# robot.net
KiCad netlist of a schematic drawn in EAGLE
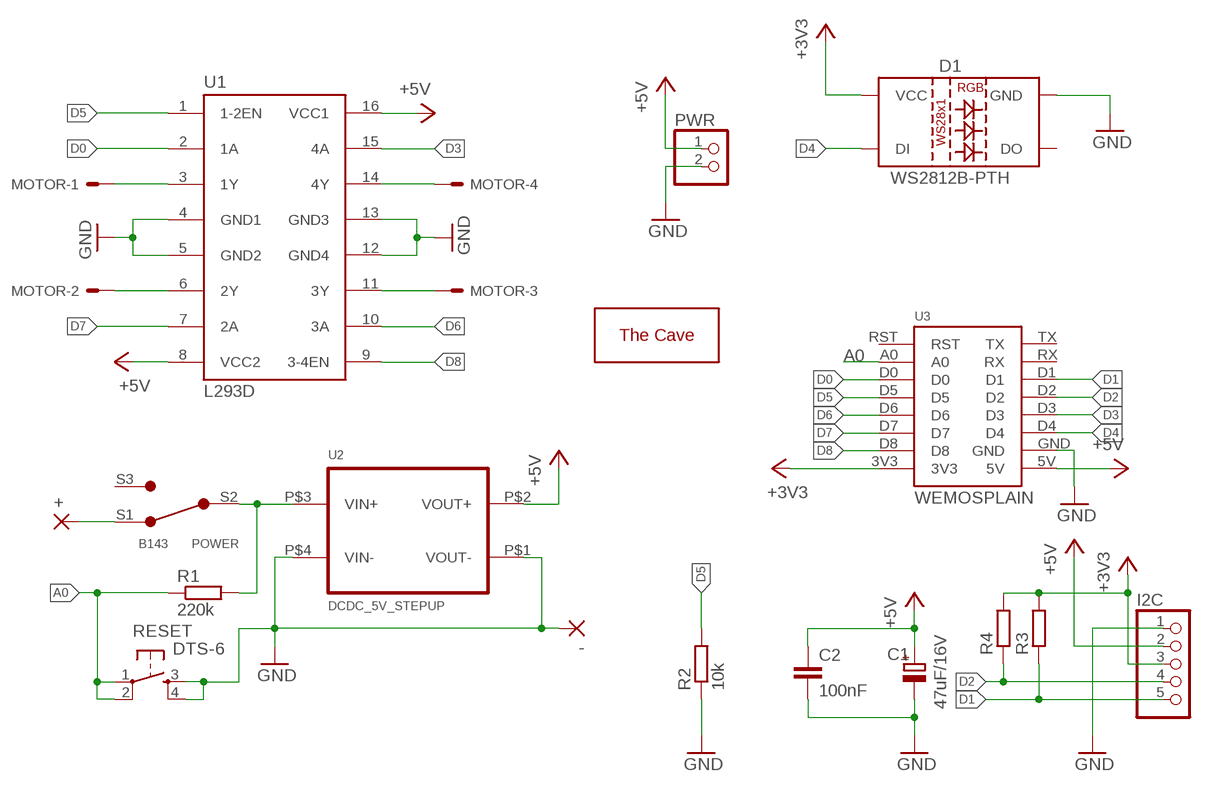
[diagram p0: schematic, sheet 1]

(export (version "E")
  (design (tool "Eeschema 10.0.6"))
  (components
    (comp (ref "+")
      (value "2,54/0,8")
      (footprint "eagle-import:2,54_0,8")
      (libsource (lib "eagle-import") (part "2,54/0,8"))
    )
    (comp (ref "-")
      (value "2,54/0,8")
      (footprint "eagle-import:2,54_0,8")
      (libsource (lib "eagle-import") (part "2,54/0,8"))
    )
    (comp (ref "C1")
      (value "47uF/16V")
      (footprint "eagle-import:E2,5-7")
      (libsource (lib "eagle-import") (part "CPOL-EUE2.5-7"))
    )
    (comp (ref "C2")
      (value "100nF")
      (footprint "eagle-import:C025-025X050")
      (libsource (lib "eagle-import") (part "C-EU025-025X050"))
    )
    (comp (ref "D1")
      (value "WS2812B-PTH")
      (footprint "eagle-import:WS2812B-PTH-KIT")
      (libsource (lib "eagle-import") (part "WS2812B-PTH"))
    )
    (comp (ref "I2C")
      (value "PINHD-1X5")
      (footprint "eagle-import:1X05")
      (libsource (lib "eagle-import") (part "PINHD-1X5"))
    )
    (comp (ref "MOTOR")
      (value "JST-XH-04-PIN-LONG-PAD")
      (footprint "eagle-import:JST-XH-04-PACKAGE-LONG-PAD")
      (libsource (lib "eagle-import") (part "JST-XH-04-PIN-LONG-PAD"))
    )
    (comp (ref "POWER")
      (value "B143")
      (footprint "eagle-import:B143")
      (libsource (lib "eagle-import") (part "B143"))
    )
    (comp (ref "PWR")
      (value "PINHD-1X2")
      (footprint "eagle-import:1X02")
      (libsource (lib "eagle-import") (part "PINHD-1X2"))
    )
    (comp (ref "R1")
      (value "220k")
      (footprint "eagle-import:0204_5")
      (libsource (lib "eagle-import") (part "R-EU_0204/5"))
    )
    (comp (ref "R2")
      (value "10k")
      (footprint "eagle-import:0204_5")
      (libsource (lib "eagle-import") (part "R-EU_0204/5"))
    )
    (comp (ref "R3")
      (value "R-EU_R0805")
      (footprint "eagle-import:R0805")
      (libsource (lib "eagle-import") (part "R-EU_R0805"))
    )
    (comp (ref "R4")
      (value "R-EU_R0805")
      (footprint "eagle-import:R0805")
      (libsource (lib "eagle-import") (part "R-EU_R0805"))
    )
    (comp (ref "RESET")
      (value "DTS-6")
      (footprint "eagle-import:DTS-6")
      (libsource (lib "eagle-import") (part "DTS-6"))
    )
    (comp (ref "U$1")
      (value "THECAVE_LOGO_NEW_TOP_SMALL")
      (footprint "eagle-import:NEW_LOGO_SMALL_TOP")
      (libsource (lib "eagle-import") (part "THECAVE_LOGO_NEW_TOP_SMALL"))
    )
    (comp (ref "U1")
      (value "L293D")
      (footprint "eagle-import:DIL16")
      (libsource (lib "eagle-import") (part "L293D"))
    )
    (comp (ref "U2")
      (value "DCDC_5V_STEPUP")
      (footprint "eagle-import:DCDC_5V_STEPUP")
      (libsource (lib "eagle-import") (part "DCDC_5V_STEPUP"))
    )
    (comp (ref "U3")
      (value "WEMOSPLAIN")
      (footprint "eagle-import:WEMOS-PLAIN")
      (libsource (lib "eagle-import") (part "WEMOSPLAIN"))
    )
  )
  (nets
    (net (code "1") (name "+3V3") (class "Default")
      (node (ref "D1") (pin "3-VCC") (pinfunction "VCC_3-VCC") (pintype "bidirectional"))
      (node (ref "I2C") (pin "3") (pinfunction "3_3") (pintype "passive"))
      (node (ref "R3") (pin "2") (pinfunction "2_2") (pintype "passive"))
      (node (ref "R4") (pin "2") (pinfunction "2_2") (pintype "passive"))
      (node (ref "U3") (pin "3V3") (pinfunction "3V3_3V3") (pintype "bidirectional"))
    )
    (net (code "2") (name "+5V") (class "Default")
      (node (ref "C1") (pin "+") (pinfunction "+_+") (pintype "passive"))
      (node (ref "C2") (pin "1") (pinfunction "1_1") (pintype "passive"))
      (node (ref "I2C") (pin "2") (pinfunction "2_2") (pintype "passive"))
      (node (ref "PWR") (pin "1") (pinfunction "1_1") (pintype "passive"))
      (node (ref "U1") (pin "16") (pinfunction "VCC1_16") (pintype "power_in"))
      (node (ref "U1") (pin "8") (pinfunction "VCC2_8") (pintype "power_in"))
      (node (ref "U2") (pin "P$2") (pinfunction "VOUT+_P$2") (pintype "power_in"))
      (node (ref "U3") (pin "5V") (pinfunction "5V_5V") (pintype "bidirectional"))
    )
    (net (code "3") (name "A0") (class "Default")
      (node (ref "R1") (pin "1") (pinfunction "1_1") (pintype "passive"))
      (node (ref "RESET") (pin "1") (pinfunction "1_1") (pintype "passive"))
      (node (ref "RESET") (pin "2") (pinfunction "2_2") (pintype "passive"))
      (node (ref "U3") (pin "A0") (pinfunction "A0_A0") (pintype "bidirectional"))
    )
    (net (code "4") (name "D0") (class "Default")
      (node (ref "U1") (pin "2") (pinfunction "1A_2") (pintype "input"))
      (node (ref "U3") (pin "D0") (pinfunction "D0_D0") (pintype "bidirectional"))
    )
    (net (code "5") (name "D1") (class "Default")
      (node (ref "I2C") (pin "5") (pinfunction "5_5") (pintype "passive"))
      (node (ref "R3") (pin "1") (pinfunction "1_1") (pintype "passive"))
      (node (ref "U3") (pin "D1") (pinfunction "D1_D1") (pintype "bidirectional"))
    )
    (net (code "6") (name "D2") (class "Default")
      (node (ref "I2C") (pin "4") (pinfunction "4_4") (pintype "passive"))
      (node (ref "R4") (pin "1") (pinfunction "1_1") (pintype "passive"))
      (node (ref "U3") (pin "D2") (pinfunction "D2_D2") (pintype "bidirectional"))
    )
    (net (code "7") (name "D3") (class "Default")
      (node (ref "U1") (pin "15") (pinfunction "4A_15") (pintype "input"))
      (node (ref "U3") (pin "D3") (pinfunction "D3_D3") (pintype "bidirectional"))
    )
    (net (code "8") (name "D4") (class "Default")
      (node (ref "D1") (pin "1-IN") (pinfunction "DI_1-IN") (pintype "bidirectional"))
      (node (ref "U3") (pin "D4") (pinfunction "D4_D4") (pintype "bidirectional"))
    )
    (net (code "9") (name "D5") (class "Default")
      (node (ref "R2") (pin "2") (pinfunction "2_2") (pintype "passive"))
      (node (ref "U1") (pin "1") (pinfunction "1-2EN_1") (pintype "input"))
      (node (ref "U3") (pin "D5") (pinfunction "D5_D5") (pintype "bidirectional"))
    )
    (net (code "10") (name "D6") (class "Default")
      (node (ref "U1") (pin "10") (pinfunction "3A_10") (pintype "input"))
      (node (ref "U3") (pin "D6") (pinfunction "D6_D6") (pintype "bidirectional"))
    )
    (net (code "11") (name "D7") (class "Default")
      (node (ref "U1") (pin "7") (pinfunction "2A_7") (pintype "input"))
      (node (ref "U3") (pin "D7") (pinfunction "D7_D7") (pintype "bidirectional"))
    )
    (net (code "12") (name "D8") (class "Default")
      (node (ref "U1") (pin "9") (pinfunction "3-4EN_9") (pintype "input"))
      (node (ref "U3") (pin "D8") (pinfunction "D8_D8") (pintype "bidirectional"))
    )
    (net (code "13") (name "GND") (class "Default")
      (node (ref "-") (pin "1") (pinfunction "P_1") (pintype "passive"))
      (node (ref "C1") (pin "-") (pinfunction "-_-") (pintype "passive"))
      (node (ref "C2") (pin "2") (pinfunction "2_2") (pintype "passive"))
      (node (ref "D1") (pin "2-GND") (pinfunction "GND_2-GND") (pintype "bidirectional"))
      (node (ref "I2C") (pin "1") (pinfunction "1_1") (pintype "passive"))
      (node (ref "PWR") (pin "2") (pinfunction "2_2") (pintype "passive"))
      (node (ref "R2") (pin "1") (pinfunction "1_1") (pintype "passive"))
      (node (ref "RESET") (pin "3") (pinfunction "3_3") (pintype "passive"))
      (node (ref "RESET") (pin "4") (pinfunction "4_4") (pintype "passive"))
      (node (ref "U1") (pin "12") (pinfunction "GND4_12") (pintype "power_in"))
      (node (ref "U1") (pin "13") (pinfunction "GND3_13") (pintype "power_in"))
      (node (ref "U1") (pin "4") (pinfunction "GND1_4") (pintype "power_in"))
      (node (ref "U1") (pin "5") (pinfunction "GND2_5") (pintype "power_in"))
      (node (ref "U2") (pin "P$1") (pinfunction "VOUT-_P$1") (pintype "power_in"))
      (node (ref "U2") (pin "P$4") (pinfunction "VIN-_P$4") (pintype "power_in"))
      (node (ref "U3") (pin "GND") (pinfunction "GND_GND") (pintype "bidirectional"))
    )
    (net (code "14") (name "Net-(+-P)") (class "Default")
      (node (ref "+") (pin "1") (pinfunction "P_1") (pintype "passive"))
      (node (ref "POWER") (pin "S1") (pinfunction "S1_S1") (pintype "bidirectional"))
    )
    (net (code "15") (name "Net-(MOTORA-S)") (class "Default")
      (node (ref "MOTOR") (pin "1") (pinfunction "S_1") (pintype "passive"))
      (node (ref "U1") (pin "3") (pinfunction "1Y_3") (pintype "output"))
    )
    (net (code "16") (name "Net-(MOTORB-S)") (class "Default")
      (node (ref "MOTOR") (pin "2") (pinfunction "S_2") (pintype "passive"))
      (node (ref "U1") (pin "6") (pinfunction "2Y_6") (pintype "output"))
    )
    (net (code "17") (name "Net-(MOTORC-S)") (class "Default")
      (node (ref "MOTOR") (pin "3") (pinfunction "S_3") (pintype "passive"))
      (node (ref "U1") (pin "11") (pinfunction "3Y_11") (pintype "output"))
    )
    (net (code "18") (name "Net-(MOTORD-S)") (class "Default")
      (node (ref "MOTOR") (pin "4") (pinfunction "S_4") (pintype "passive"))
      (node (ref "U1") (pin "14") (pinfunction "4Y_14") (pintype "output"))
    )
    (net (code "19") (name "Net-(POWER-COM)") (class "Default")
      (node (ref "POWER") (pin "S2") (pinfunction "COM_S2") (pintype "bidirectional"))
      (node (ref "R1") (pin "2") (pinfunction "2_2") (pintype "passive"))
      (node (ref "U2") (pin "P$3") (pinfunction "VIN+_P$3") (pintype "power_in"))
    )
    (net (code "20") (name "unconnected-(D1-DO-Pad4-OUT)") (class "Default")
      (node (ref "D1") (pin "4-OUT") (pinfunction "DO_4-OUT") (pintype "bidirectional"))
    )
    (net (code "21") (name "unconnected-(POWER-S2-PadS3)") (class "Default")
      (node (ref "POWER") (pin "S3") (pinfunction "S2_S3") (pintype "bidirectional"))
    )
    (net (code "22") (name "unconnected-(U3-PadRST)") (class "Default")
      (node (ref "U3") (pin "RST") (pinfunction "RST_RST") (pintype "bidirectional"))
    )
    (net (code "23") (name "unconnected-(U3-PadRX)") (class "Default")
      (node (ref "U3") (pin "RX") (pinfunction "RX_RX") (pintype "bidirectional"))
    )
    (net (code "24") (name "unconnected-(U3-PadTX)") (class "Default")
      (node (ref "U3") (pin "TX") (pinfunction "TX_TX") (pintype "bidirectional"))
    )
  )
)
